# buck_converter15A-5V.net
KiCad netlist of a schematic drawn in Altium Designer
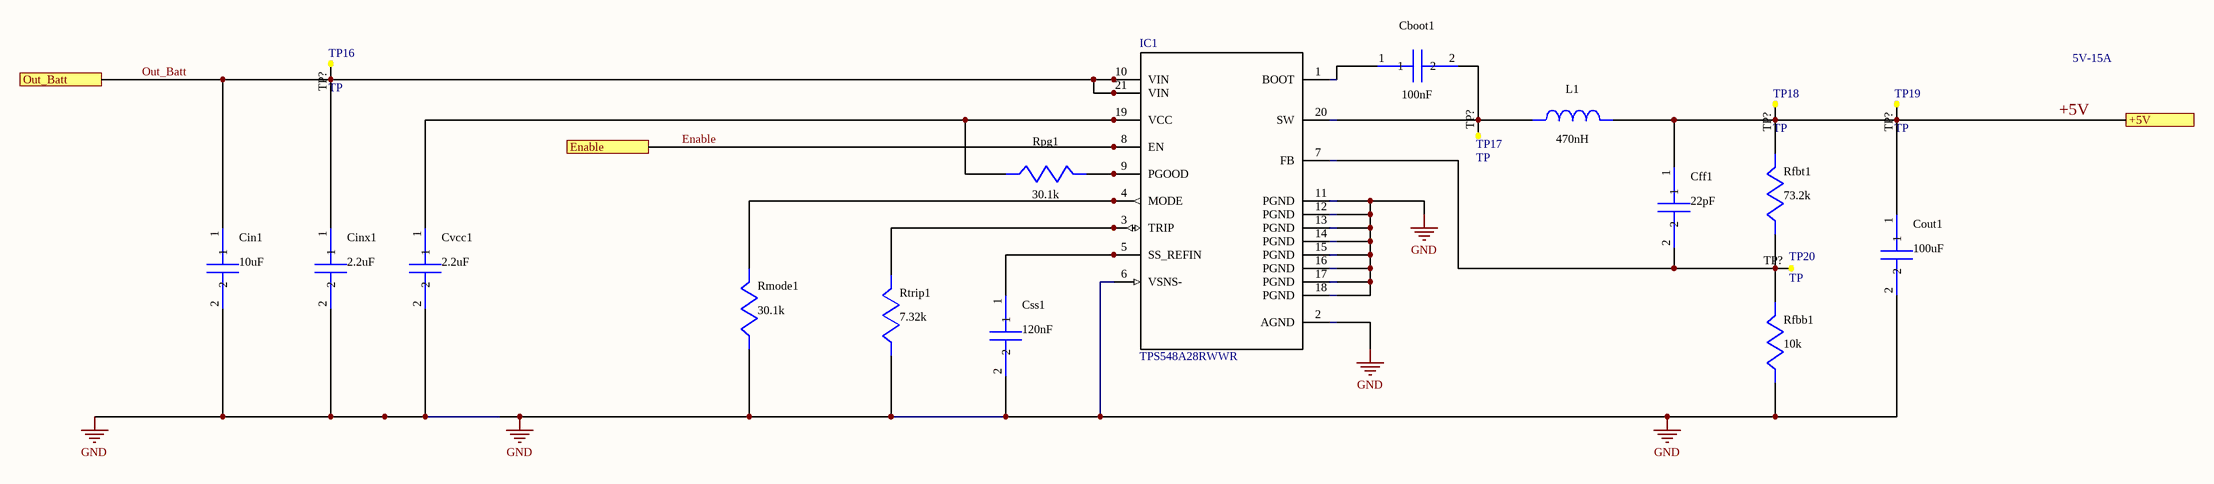
[diagram p0: buck_converter15A-5V.schdoc]

(export (version "E")
  (design (tool "Eeschema 10.0.6"))
  (components
    (comp (ref "Cboot1")
      (value "100nF")
      (footprint "CAPC1005X55N")
      (description "EMK107B7104KA-T")
      (fields (field (name "Comment") "EMK105 B7104KVHF"))
      (libsource (lib "TI WEBENCH") (part "Cboot"))
    )
    (comp (ref "Cff1")
      (value "C1005C0G1H220J")
      (footprint "CAPC1005X55N")
      (description "C0402C240J3GACTU")
      (fields (field (name "C1005C0G1H220J") "22pF"))
      (libsource (lib "TI WEBENCH") (part "Cff"))
    )
    (comp (ref "Cin1")
      (value "10uF")
      (footprint "CAPC3216X200N")
      (description "GRM31CR71E106KA1")
      (fields
        (field (name "MANUFACTURER PART NUMBER") "GRM31CR71E106KA12L")
        (field (name "Comment") "GCJ31CC71E106K")
      )
      (libsource (lib "TI WEBENCH") (part "Cin"))
    )
    (comp (ref "Cinx1")
      (value "2.2uF")
      (footprint "CAPC1608X80N")
      (description "C1608X7R1A225K08")
      (fields
        (field (name "MANUFACTURER PART NUMBER") "C1608X7R1A225K080AC")
        (field (name "Comment") "GCM188C71A225K")
      )
      (libsource (lib "TI WEBENCH") (part "Cinx"))
    )
    (comp (ref "Cout1")
      (value "100uF")
      (footprint "CAPC3225X270N")
      (description "CUSTOM1")
      (fields
        (field (name "MANUFACTURER PART NUMBER") "GENERIC_CAPACITOR")
        (field (name "Comment") "EMK325ABJ107MM-T")
      )
      (libsource (lib "TI WEBENCH") (part "Cout"))
    )
    (comp (ref "Css1")
      (value "120nF")
      (footprint "CAPC1005X55N")
      (description "GRM155R61A124KE1")
      (fields
        (field (name "MANUFACTURER PART NUMBER") "GRM155R61A124KE19D")
        (field (name "Comment") "C1608X7R1H154K")
      )
      (libsource (lib "TI WEBENCH") (part "Css"))
    )
    (comp (ref "Cvcc1")
      (value "2.2uF")
      (footprint "CAPC1608X80N")
      (description "GRM188R71A225KE1")
      (fields
        (field (name "MANUFACTURER PART NUMBER") "GRM188R71A225KE15D")
        (field (name "Comment") "GCM188C71A225K")
      )
      (libsource (lib "TI WEBENCH") (part "Cvcc"))
    )
    (comp (ref "IC1")
      (value "TPS548A28RWWR")
      (footprint "RWW0021A")
      (description "No Description Available")
      (fields
        (field (name "MANUFACTURER") "Texas Instruments")
        (field (name "COPYRIGHT") "Copyright (C) 2018 Accelerated Designs. All rights reserved")
      )
      (libsource (lib "TPS548B(vqfn-hr-21)") (part "TPS548A28RWWR"))
    )
    (comp (ref "L1")
      (value "470nH")
      (footprint "IHLP4040DZERR47M11")
      (description "IHLP4040DZERR47M")
      (fields (field (name "MANUFACTURER PART NUMBER") "IHLP4040DZERR47M11"))
      (libsource (lib "TI WEBENCH") (part "L1"))
    )
    (comp (ref "Rfbb1")
      (value "10k")
      (footprint "SMM02040D1501BB300")
      (description "CRCW040210K0FKED")
      (fields (field (name "Comment") "SMM0204 50 10K 1 %"))
      (libsource (lib "TI WEBENCH") (part "Rfbb"))
    )
    (comp (ref "Rfbt1")
      (value "73.2k")
      (footprint "ERJ2RKD1004X")
      (description "CRCW040273K2FKED")
      (fields (field (name "Comment") "SMM0204 50 73K2 1 %"))
      (libsource (lib "TI WEBENCH") (part "Rfbt"))
    )
    (comp (ref "Rmode1")
      (value "30.1k")
      (footprint "SMM02040D1501BB300")
      (description "CRCW040230K1FKED")
      (fields (field (name "Comment") "SMM0204 50 30K1 1 %"))
      (libsource (lib "TI WEBENCH") (part "Rmode"))
    )
    (comp (ref "Rpg1")
      (value "30.1k")
      (footprint "SMM02040D1501BB300")
      (description "CRCW040230K1FKED")
      (fields (field (name "Comment") "SMM0204 50 30K1 1 %"))
      (libsource (lib "TI WEBENCH") (part "Rpg"))
    )
    (comp (ref "Rtrip1")
      (value "7.32k")
      (footprint "ERJ2RKD1004X")
      (description "SMM0204 50 7K32 1 %")
      (fields (field (name "MANUFACTURER PART NUMBER") "CRCW04027K32FKED"))
      (libsource (lib "TI WEBENCH") (part "Rtrip"))
    )
    (comp (ref "TP16")
      (value "TP")
      (footprint "Test_Point0.5x0.5")
      (libsource (lib "TP_0.6x0.6") (part "TEst_Point_0.5x0.5"))
    )
    (comp (ref "TP17")
      (value "TP")
      (footprint "Test_Point0.5x0.5")
      (libsource (lib "TP_0.6x0.6") (part "TEst_Point_0.5x0.5"))
    )
    (comp (ref "TP18")
      (value "TP")
      (footprint "Test_Point0.5x0.5")
      (libsource (lib "TP_0.6x0.6") (part "TEst_Point_0.5x0.5"))
    )
    (comp (ref "TP19")
      (value "TP")
      (footprint "Test_Point0.5x0.5")
      (libsource (lib "TP_0.6x0.6") (part "TEst_Point_0.5x0.5"))
    )
    (comp (ref "TP20")
      (value "TP")
      (footprint "Test_Point0.5x0.5")
      (libsource (lib "TP_0.6x0.6") (part "TEst_Point_0.5x0.5"))
    )
  )
  (nets
    (net (code "1") (name "/+5V") (class "Default")
      (node (ref "Cff1") (pin "1") (pinfunction "1_1") (pintype "passive"))
      (node (ref "Cout1") (pin "1") (pinfunction "1_1") (pintype "passive"))
      (node (ref "L1") (pin "1") (pinfunction "1_1") (pintype "passive"))
      (node (ref "Rfbt1") (pin "1") (pinfunction "1_1") (pintype "passive"))
      (node (ref "TP18") (pin "TP?") (pinfunction "TP_TP?") (pintype "passive"))
      (node (ref "TP19") (pin "TP?") (pinfunction "TP_TP?") (pintype "passive"))
    )
    (net (code "2") (name "/Enable") (class "Default")
      (node (ref "IC1") (pin "8") (pinfunction "EN_8") (pintype "power_in"))
    )
    (net (code "3") (name "/Out_Batt") (class "Default")
      (node (ref "Cin1") (pin "1") (pinfunction "1_1") (pintype "passive"))
      (node (ref "Cinx1") (pin "1") (pinfunction "1_1") (pintype "passive"))
      (node (ref "IC1") (pin "10") (pinfunction "VIN_10") (pintype "power_in"))
      (node (ref "IC1") (pin "21") (pinfunction "VIN_21") (pintype "power_in"))
      (node (ref "TP16") (pin "TP?") (pinfunction "TP_TP?") (pintype "passive"))
    )
    (net (code "4") (name "GND") (class "Default")
      (node (ref "Cin1") (pin "2") (pinfunction "2_2") (pintype "passive"))
      (node (ref "Cinx1") (pin "2") (pinfunction "2_2") (pintype "passive"))
      (node (ref "Cout1") (pin "2") (pinfunction "2_2") (pintype "passive"))
      (node (ref "Css1") (pin "2") (pinfunction "2_2") (pintype "passive"))
      (node (ref "Cvcc1") (pin "2") (pinfunction "2_2") (pintype "passive"))
      (node (ref "IC1") (pin "11") (pinfunction "PGND_11") (pintype "power_in"))
      (node (ref "IC1") (pin "12") (pinfunction "PGND_12") (pintype "power_in"))
      (node (ref "IC1") (pin "13") (pinfunction "PGND_13") (pintype "power_in"))
      (node (ref "IC1") (pin "14") (pinfunction "PGND_14") (pintype "power_in"))
      (node (ref "IC1") (pin "15") (pinfunction "PGND_15") (pintype "power_in"))
      (node (ref "IC1") (pin "16") (pinfunction "PGND_16") (pintype "power_in"))
      (node (ref "IC1") (pin "17") (pinfunction "PGND_17") (pintype "power_in"))
      (node (ref "IC1") (pin "18") (pinfunction "PGND_18") (pintype "power_in"))
      (node (ref "IC1") (pin "2") (pinfunction "AGND_2") (pintype "power_in"))
      (node (ref "IC1") (pin "6") (pinfunction "VSNS-_6") (pintype "input"))
      (node (ref "Rfbb1") (pin "2") (pinfunction "2_2") (pintype "passive"))
      (node (ref "Rmode1") (pin "2") (pinfunction "2_2") (pintype "passive"))
      (node (ref "Rtrip1") (pin "2") (pinfunction "2_2") (pintype "passive"))
    )
    (net (code "5") (name "Net-(IC1-BOOT)") (class "Default")
      (node (ref "Cboot1") (pin "1") (pinfunction "1_1") (pintype "passive"))
      (node (ref "IC1") (pin "1") (pinfunction "BOOT_1") (pintype "power_in"))
    )
    (net (code "6") (name "Net-(IC1-FB)") (class "Default")
      (node (ref "Cff1") (pin "2") (pinfunction "2_2") (pintype "passive"))
      (node (ref "IC1") (pin "7") (pinfunction "FB_7") (pintype "power_in"))
      (node (ref "Rfbb1") (pin "1") (pinfunction "1_1") (pintype "passive"))
      (node (ref "Rfbt1") (pin "2") (pinfunction "2_2") (pintype "passive"))
      (node (ref "TP20") (pin "TP?") (pinfunction "TP_TP?") (pintype "passive"))
    )
    (net (code "7") (name "Net-(IC1-MODE)") (class "Default")
      (node (ref "IC1") (pin "4") (pinfunction "MODE_4") (pintype "output"))
      (node (ref "Rmode1") (pin "1") (pinfunction "1_1") (pintype "passive"))
    )
    (net (code "8") (name "Net-(IC1-PGOOD)") (class "Default")
      (node (ref "IC1") (pin "9") (pinfunction "PGOOD_9") (pintype "open_collector"))
      (node (ref "Rpg1") (pin "1") (pinfunction "1_1") (pintype "passive"))
    )
    (net (code "9") (name "Net-(IC1-SS_REFIN)") (class "Default")
      (node (ref "Css1") (pin "1") (pinfunction "1_1") (pintype "passive"))
      (node (ref "IC1") (pin "5") (pinfunction "SS_REFIN_5") (pintype "power_in"))
    )
    (net (code "10") (name "Net-(IC1-SW)") (class "Default")
      (node (ref "Cboot1") (pin "2") (pinfunction "2_2") (pintype "passive"))
      (node (ref "IC1") (pin "20") (pinfunction "SW_20") (pintype "power_in"))
      (node (ref "L1") (pin "2") (pinfunction "2_2") (pintype "passive"))
      (node (ref "TP17") (pin "TP?") (pinfunction "TP_TP?") (pintype "passive"))
    )
    (net (code "11") (name "Net-(IC1-TRIP)") (class "Default")
      (node (ref "IC1") (pin "3") (pinfunction "TRIP_3") (pintype "bidirectional"))
      (node (ref "Rtrip1") (pin "1") (pinfunction "1_1") (pintype "passive"))
    )
    (net (code "12") (name "Net-(IC1-VCC)") (class "Default")
      (node (ref "Cvcc1") (pin "1") (pinfunction "1_1") (pintype "passive"))
      (node (ref "IC1") (pin "19") (pinfunction "VCC_19") (pintype "power_in"))
      (node (ref "Rpg1") (pin "2") (pinfunction "2_2") (pintype "passive"))
    )
  )
)
